# openScale_v04.net
KiCad netlist of a schematic drawn in EAGLE
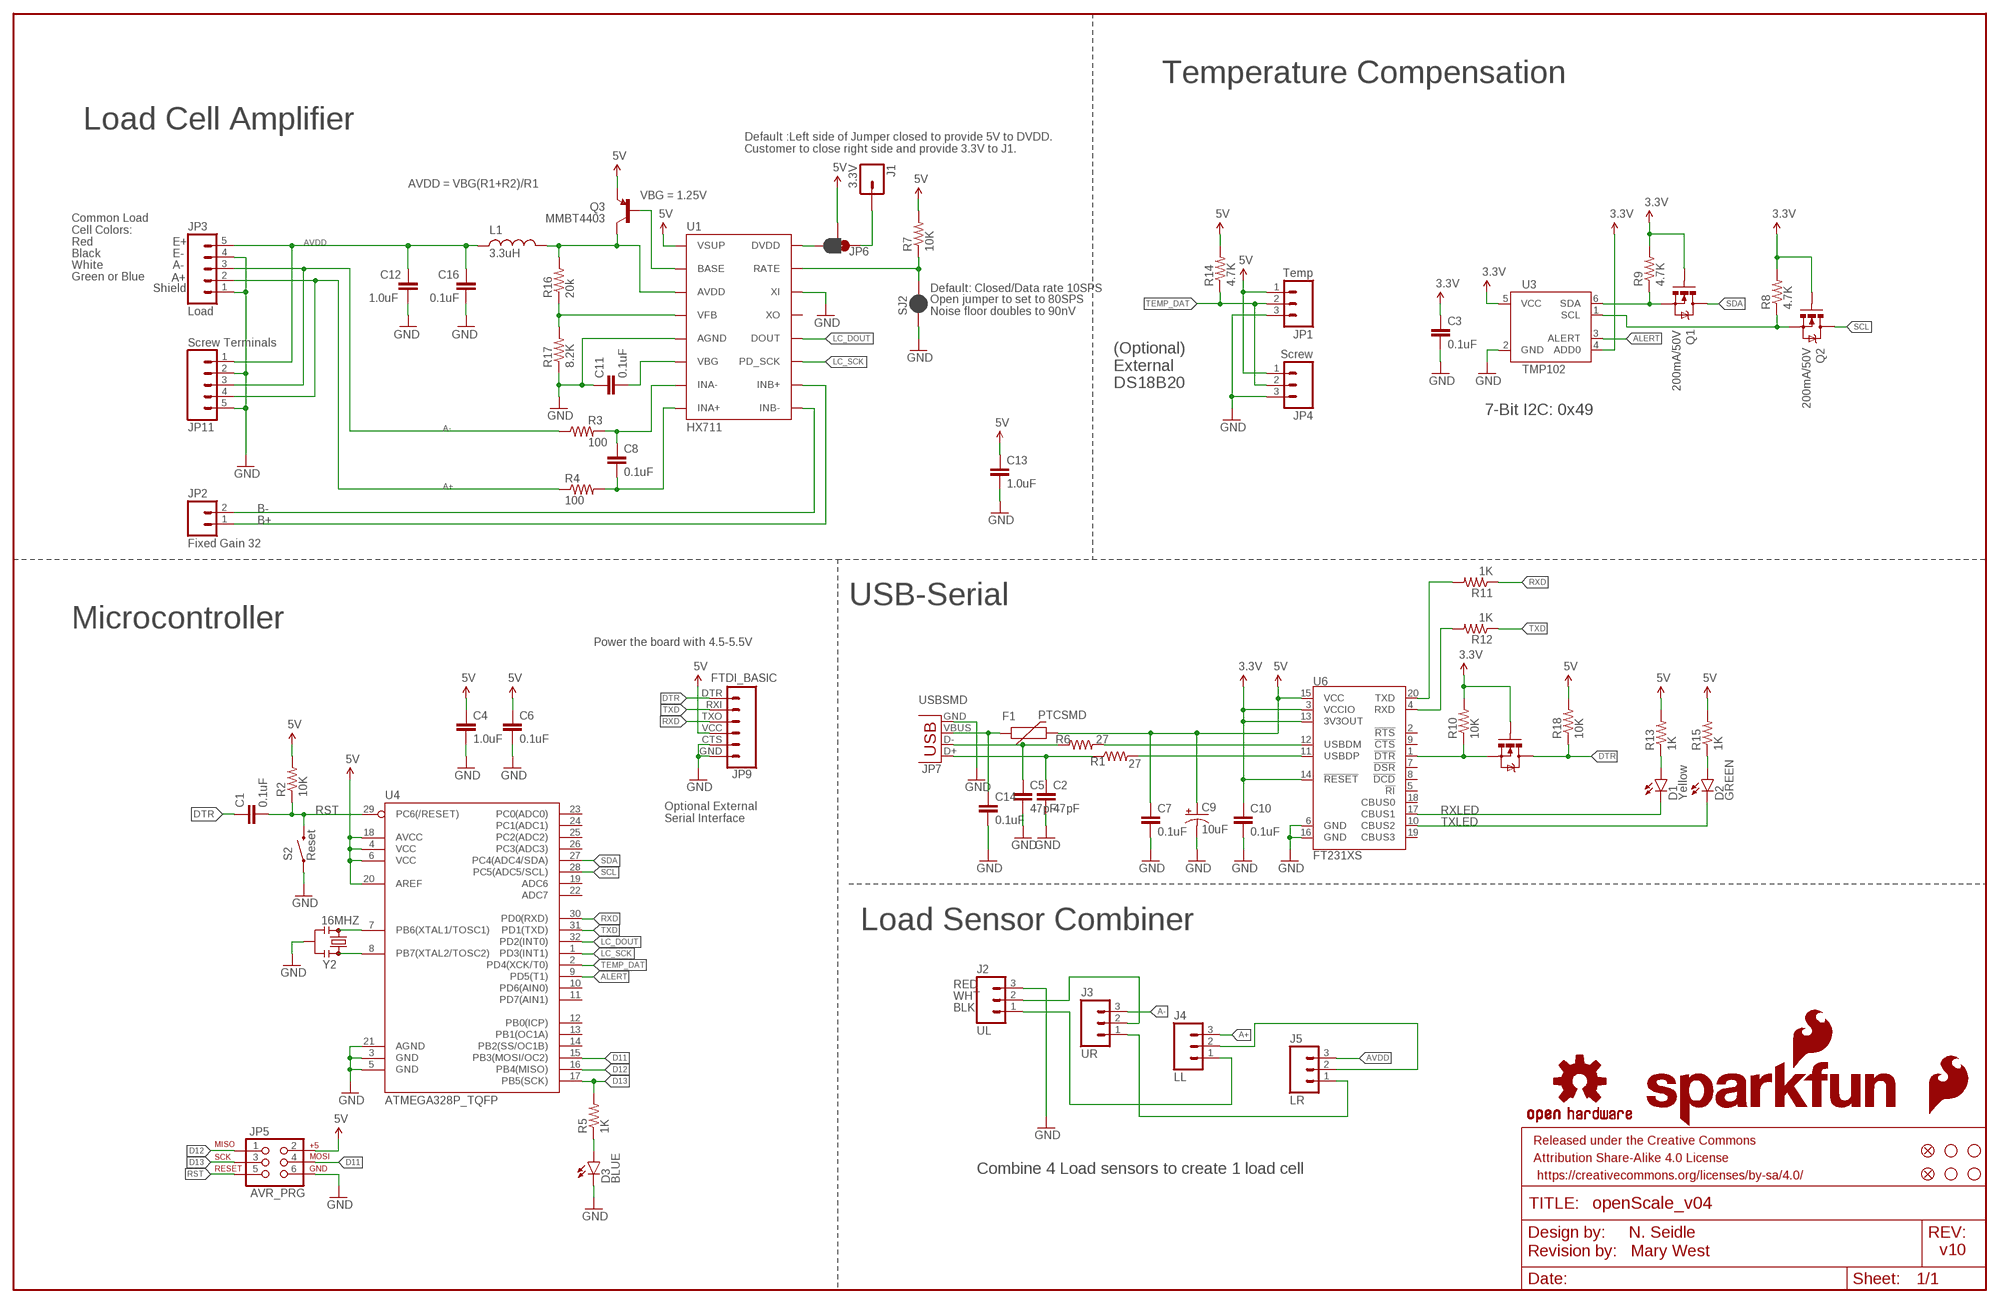
[diagram p0: schematic, sheet 1]

(export (version "E")
  (design (tool "Eeschema 10.0.6"))
  (components
    (comp (ref "C1")
      (value "0.1uF")
      (footprint "eagle-import:0603-CAP")
      (libsource (lib "eagle-import") (part "0.1UF-25V(+80/-20%)(0603)"))
    )
    (comp (ref "C2")
      (value "47pF")
      (footprint "eagle-import:0603-CAP")
      (libsource (lib "eagle-import") (part "47PF-50V-5%(0603)"))
    )
    (comp (ref "C3")
      (value "0.1uF")
      (footprint "eagle-import:0603-CAP")
      (libsource (lib "eagle-import") (part "0.1UF-25V(+80/-20%)(0603)"))
    )
    (comp (ref "C4")
      (value "1.0uF")
      (footprint "eagle-import:0603-CAP")
      (libsource (lib "eagle-import") (part "1.0UF-16V-10%(0603)"))
    )
    (comp (ref "C5")
      (value "47pF")
      (footprint "eagle-import:0603-CAP")
      (libsource (lib "eagle-import") (part "47PF-50V-5%(0603)"))
    )
    (comp (ref "C6")
      (value "0.1uF")
      (footprint "eagle-import:0603-CAP")
      (libsource (lib "eagle-import") (part "0.1UF-25V(+80/-20%)(0603)"))
    )
    (comp (ref "C7")
      (value "0.1uF")
      (footprint "eagle-import:0603-CAP")
      (libsource (lib "eagle-import") (part "0.1UF-25V(+80/-20%)(0603)"))
    )
    (comp (ref "C8")
      (value "0.1uF")
      (footprint "eagle-import:0603-CAP")
      (libsource (lib "eagle-import") (part "0.1UF-25V(+80/-20%)(0603)"))
    )
    (comp (ref "C9")
      (value "10uF")
      (footprint "eagle-import:EIA3216")
      (libsource (lib "eagle-import") (part "10UF-16V-10%(TANT)"))
    )
    (comp (ref "C10")
      (value "0.1uF")
      (footprint "eagle-import:0603-CAP")
      (libsource (lib "eagle-import") (part "0.1UF-25V(+80/-20%)(0603)"))
    )
    (comp (ref "C11")
      (value "0.1uF")
      (footprint "eagle-import:0603-CAP")
      (libsource (lib "eagle-import") (part "0.1UF-25V(+80/-20%)(0603)"))
    )
    (comp (ref "C12")
      (value "1.0uF")
      (footprint "eagle-import:0603-CAP")
      (libsource (lib "eagle-import") (part "1.0UF-16V-10%(0603)"))
    )
    (comp (ref "C13")
      (value "1.0uF")
      (footprint "eagle-import:0603-CAP")
      (libsource (lib "eagle-import") (part "1.0UF-16V-10%(0603)"))
    )
    (comp (ref "C14")
      (value "0.1uF")
      (footprint "eagle-import:0603-CAP")
      (libsource (lib "eagle-import") (part "0.1UF-25V(+80/-20%)(0603)"))
    )
    (comp (ref "C16")
      (value "0.1uF")
      (footprint "eagle-import:0603-CAP")
      (libsource (lib "eagle-import") (part "0.1UF-25V(+80/-20%)(0603)"))
    )
    (comp (ref "D1")
      (value "Yellow")
      (footprint "eagle-import:LED-1206")
      (libsource (lib "eagle-import") (part "LED-YELLOWLILYPAD"))
    )
    (comp (ref "D2")
      (value "GREEN")
      (footprint "eagle-import:LED-1206")
      (libsource (lib "eagle-import") (part "LED-GREEN1206"))
    )
    (comp (ref "D3")
      (value "BLUE")
      (footprint "eagle-import:LED-1206")
      (libsource (lib "eagle-import") (part "LED-BLUE1206"))
    )
    (comp (ref "F1")
      (value "PTCSMD")
      (footprint "eagle-import:PTC-1206")
      (libsource (lib "eagle-import") (part "PTCSMD"))
    )
    (comp (ref "FID1")
      (value "FIDUCIALUFIDUCIAL")
      (footprint "eagle-import:MICRO-FIDUCIAL")
      (libsource (lib "eagle-import") (part "FIDUCIALUFIDUCIAL"))
    )
    (comp (ref "FID2")
      (value "FIDUCIALUFIDUCIAL")
      (footprint "eagle-import:MICRO-FIDUCIAL")
      (libsource (lib "eagle-import") (part "FIDUCIALUFIDUCIAL"))
    )
    (comp (ref "FRAME1")
      (value "FRAME-LEDGER")
      (footprint "eagle-import:CREATIVE_COMMONS")
      (fields (field (name "DESIGNER") "N. Seidle") (field (name "VERSION") "v02"))
      (libsource (lib "eagle-import") (part "FRAME-LEDGER"))
    )
    (comp (ref "J1")
      (value "3.3V")
      (footprint "eagle-import:1X01")
      (libsource (lib "eagle-import") (part "M01PTH"))
    )
    (comp (ref "J2")
      (value "UL")
      (footprint "eagle-import:1X03")
      (libsource (lib "eagle-import") (part "M03PTH"))
    )
    (comp (ref "J3")
      (value "UR")
      (footprint "eagle-import:1X03")
      (libsource (lib "eagle-import") (part "M03PTH"))
    )
    (comp (ref "J4")
      (value "LL")
      (footprint "eagle-import:1X03")
      (libsource (lib "eagle-import") (part "M03PTH"))
    )
    (comp (ref "J5")
      (value "LR")
      (footprint "eagle-import:1X03")
      (libsource (lib "eagle-import") (part "M03PTH"))
    )
    (comp (ref "JP1")
      (value "Temp")
      (footprint "eagle-import:1X03_NO_SILK")
      (libsource (lib "eagle-import") (part "M031X03_NO_SILK"))
    )
    (comp (ref "JP2")
      (value "Fixed Gain 32")
      (footprint "eagle-import:1X02")
      (libsource (lib "eagle-import") (part "M02PTH"))
    )
    (comp (ref "JP3")
      (value "Load")
      (footprint "eagle-import:1X05_NO_SILK")
      (libsource (lib "eagle-import") (part "M05NO_SILK"))
    )
    (comp (ref "JP4")
      (value "Screw")
      (footprint "eagle-import:SCREWTERMINAL-3.5MM-3_LOCK.007S")
      (libsource (lib "eagle-import") (part "M03SCREW_LOCK"))
    )
    (comp (ref "JP5")
      (value "AVR_PRG")
      (footprint "eagle-import:2X3")
      (libsource (lib "eagle-import") (part "AVR_SPI_PRG_6PTH"))
    )
    (comp (ref "JP6")
      (value "JUMPER-PAD-3-2OF3_NC_BY_PASTE")
      (footprint "eagle-import:PAD-JUMPER-3-2OF3_NC_BY_PASTE_YES_SILK_FULL_BOX")
      (libsource (lib "eagle-import") (part "JUMPER-PAD-3-2OF3_NC_BY_PASTE"))
    )
    (comp (ref "JP7")
      (value "USBSMD")
      (footprint "eagle-import:USB-MINIB")
      (libsource (lib "eagle-import") (part "USBSMD"))
    )
    (comp (ref "JP9")
      (value "FTDI_BASIC")
      (footprint "eagle-import:FTDI_BASIC")
      (libsource (lib "eagle-import") (part "FTDI_BASICPTH"))
    )
    (comp (ref "JP11")
      (value "Screw Terminals")
      (footprint "eagle-import:SCREWTERMINAL-3.5MM-5")
      (libsource (lib "eagle-import") (part "M05SCREW"))
    )
    (comp (ref "L1")
      (value "3.3uH")
      (footprint "eagle-import:0805")
      (libsource (lib "eagle-import") (part "INDUCTOR0805-IND"))
    )
    (comp (ref "LOGO2")
      (value "OSHW-LOGOS")
      (footprint "eagle-import:OSHW-LOGO-S")
      (libsource (lib "eagle-import") (part "OSHW-LOGOS"))
    )
    (comp (ref "LOGO3")
      (value "SFE_LOGO_FLAME.1_INCH")
      (footprint "eagle-import:SFE_LOGO_FLAME_.1")
      (libsource (lib "eagle-import") (part "SFE_LOGO_FLAME.1_INCH"))
    )
    (comp (ref "LOGO4")
      (value "SFE_LOGO_NAME_FLAME.1_INCH")
      (footprint "eagle-import:SFE_LOGO_NAME_FLAME_.1")
      (libsource (lib "eagle-import") (part "SFE_LOGO_NAME_FLAME.1_INCH"))
    )
    (comp (ref "Q1")
      (value "200mA/50V")
      (footprint "eagle-import:SOT23-3")
      (libsource (lib "eagle-import") (part "MOSFET-NCHANNELBSS138"))
    )
    (comp (ref "Q2")
      (value "200mA/50V")
      (footprint "eagle-import:SOT23-3")
      (libsource (lib "eagle-import") (part "MOSFET-NCHANNELBSS138"))
    )
    (comp (ref "Q3")
      (value "MMBT4403")
      (footprint "eagle-import:SOT23-3")
      (libsource (lib "eagle-import") (part "TRANSISTOR_PNPMMBT4403"))
    )
    (comp (ref "Q4")
      (value "MOSFET-NCHANNEL2N7002PW")
      (footprint "eagle-import:SOT323")
      (libsource (lib "eagle-import") (part "MOSFET-NCHANNEL2N7002PW"))
    )
    (comp (ref "R1")
      (value "27")
      (footprint "eagle-import:0603")
      (libsource (lib "eagle-import") (part "27OHM1/10W1%(0603)"))
    )
    (comp (ref "R2")
      (value "10K")
      (footprint "eagle-import:0603-RES")
      (libsource (lib "eagle-import") (part "10KOHM-1/10W-1%(0603)0603"))
    )
    (comp (ref "R3")
      (value "100")
      (footprint "eagle-import:0603-RES")
      (libsource (lib "eagle-import") (part "100OHM-1/10W-1%(0603)"))
    )
    (comp (ref "R4")
      (value "100")
      (footprint "eagle-import:0603-RES")
      (libsource (lib "eagle-import") (part "100OHM-1/10W-1%(0603)"))
    )
    (comp (ref "R5")
      (value "1K")
      (footprint "eagle-import:0603-RES")
      (libsource (lib "eagle-import") (part "1KOHM-1/10W-1%(0603)"))
    )
    (comp (ref "R6")
      (value "27")
      (footprint "eagle-import:0603")
      (libsource (lib "eagle-import") (part "27OHM1/10W1%(0603)"))
    )
    (comp (ref "R7")
      (value "10K")
      (footprint "eagle-import:0603-RES")
      (libsource (lib "eagle-import") (part "10KOHM-1/10W-1%(0603)0603"))
    )
    (comp (ref "R8")
      (value "4.7K")
      (footprint "eagle-import:0603-RES")
      (libsource (lib "eagle-import") (part "4.7KOHM-1/10W-1%(0603)"))
    )
    (comp (ref "R9")
      (value "4.7K")
      (footprint "eagle-import:0603-RES")
      (libsource (lib "eagle-import") (part "4.7KOHM-1/10W-1%(0603)"))
    )
    (comp (ref "R10")
      (value "10K")
      (footprint "eagle-import:0603-RES")
      (libsource (lib "eagle-import") (part "10KOHM-1/10W-1%(0603)0603"))
    )
    (comp (ref "R11")
      (value "1K")
      (footprint "eagle-import:0603-RES")
      (libsource (lib "eagle-import") (part "1KOHM-1/10W-1%(0603)"))
    )
    (comp (ref "R12")
      (value "1K")
      (footprint "eagle-import:0603-RES")
      (libsource (lib "eagle-import") (part "1KOHM-1/10W-1%(0603)"))
    )
    (comp (ref "R13")
      (value "1K")
      (footprint "eagle-import:0603-RES")
      (libsource (lib "eagle-import") (part "1KOHM-1/10W-1%(0603)"))
    )
    (comp (ref "R14")
      (value "4.7K")
      (footprint "eagle-import:0603-RES")
      (libsource (lib "eagle-import") (part "4.7KOHM-1/10W-1%(0603)"))
    )
    (comp (ref "R15")
      (value "1K")
      (footprint "eagle-import:0603-RES")
      (libsource (lib "eagle-import") (part "1KOHM-1/10W-1%(0603)"))
    )
    (comp (ref "R16")
      (value "20k")
      (footprint "eagle-import:0603-RES")
      (libsource (lib "eagle-import") (part "20KOHM1/10W1%(0603)"))
    )
    (comp (ref "R17")
      (value "8.2K")
      (footprint "eagle-import:0603-RES")
      (libsource (lib "eagle-import") (part "8.2KOHM-1/10W-5%(0603)"))
    )
    (comp (ref "R18")
      (value "10K")
      (footprint "eagle-import:0603-RES")
      (libsource (lib "eagle-import") (part "10KOHM-1/10W-1%(0603)0603"))
    )
    (comp (ref "S2")
      (value "Reset")
      (footprint "eagle-import:TACTILE-SWITCH-SMD")
      (libsource (lib "eagle-import") (part "SWITCH-MOMENTARY-2SMD"))
    )
    (comp (ref "SJ2")
      (value "JUMPER-PAD-2-NC_BY_PASTE")
      (footprint "eagle-import:PAD-JUMPER-2-NC_BY_PASTE_YES_SILK")
      (libsource (lib "eagle-import") (part "JUMPER-PAD-2-NC_BY_PASTE"))
    )
    (comp (ref "STANDOFF1")
      (value "STAND-OFF")
      (footprint "eagle-import:STAND-OFF")
      (libsource (lib "eagle-import") (part "STAND-OFF"))
    )
    (comp (ref "STANDOFF2")
      (value "STAND-OFF")
      (footprint "eagle-import:STAND-OFF")
      (libsource (lib "eagle-import") (part "STAND-OFF"))
    )
    (comp (ref "STANDOFF3")
      (value "STAND-OFF")
      (footprint "eagle-import:STAND-OFF")
      (libsource (lib "eagle-import") (part "STAND-OFF"))
    )
    (comp (ref "STANDOFF4")
      (value "STAND-OFF")
      (footprint "eagle-import:STAND-OFF")
      (libsource (lib "eagle-import") (part "STAND-OFF"))
    )
    (comp (ref "U1")
      (value "HX711")
      (footprint "eagle-import:SO16")
      (libsource (lib "eagle-import") (part "HX711HX711"))
    )
    (comp (ref "U3")
      (value "TMP102")
      (footprint "eagle-import:SOT563")
      (libsource (lib "eagle-import") (part "TMP102"))
    )
    (comp (ref "U4")
      (value "ATMEGA328P_TQFP")
      (footprint "eagle-import:TQFP32-08")
      (libsource (lib "eagle-import") (part "ATMEGA328P_TQFP"))
    )
    (comp (ref "U6")
      (value "FT231XS")
      (footprint "eagle-import:SSOP20_L")
      (libsource (lib "eagle-import") (part "FT231XS"))
    )
    (comp (ref "Y2")
      (value "16MHZ")
      (footprint "eagle-import:RESONATOR-SMD")
      (libsource (lib "eagle-import") (part "RESONATOR16MHZ"))
    )
  )
  (nets
    (net (code "1") (name "/B+") (class "Default")
      (node (ref "JP2") (pin "1") (pinfunction "1_1") (pintype "passive"))
      (node (ref "U1") (pin "10") (pinfunction "INB+_10") (pintype "bidirectional"))
    )
    (net (code "2") (name "/B-") (class "Default")
      (node (ref "JP2") (pin "2") (pinfunction "2_2") (pintype "passive"))
      (node (ref "U1") (pin "9") (pinfunction "INB-_9") (pintype "bidirectional"))
    )
    (net (code "3") (name "/RXLED") (class "Default")
      (node (ref "D1") (pin "C") (pinfunction "C_C") (pintype "passive"))
      (node (ref "U6") (pin "17") (pinfunction "CBUS1_17") (pintype "bidirectional"))
    )
    (net (code "4") (name "/TXLED") (class "Default")
      (node (ref "D2") (pin "C") (pinfunction "C_C") (pintype "passive"))
      (node (ref "U6") (pin "10") (pinfunction "CBUS2_10") (pintype "bidirectional"))
    )
    (net (code "5") (name "3.3V") (class "Default")
      (node (ref "C10") (pin "1") (pinfunction "1_1") (pintype "passive"))
      (node (ref "C3") (pin "1") (pinfunction "1_1") (pintype "passive"))
      (node (ref "Q1") (pin "1") (pinfunction "G_1") (pintype "passive"))
      (node (ref "Q2") (pin "1") (pinfunction "G_1") (pintype "passive"))
      (node (ref "Q4") (pin "1") (pinfunction "G_1") (pintype "passive"))
      (node (ref "R10") (pin "2") (pinfunction "2_2") (pintype "passive"))
      (node (ref "R8") (pin "2") (pinfunction "2_2") (pintype "passive"))
      (node (ref "R9") (pin "2") (pinfunction "2_2") (pintype "passive"))
      (node (ref "U3") (pin "4") (pinfunction "ADD0_4") (pintype "bidirectional"))
      (node (ref "U3") (pin "5") (pinfunction "VCC_5") (pintype "bidirectional"))
      (node (ref "U6") (pin "13") (pinfunction "3V3OUT_13") (pintype "bidirectional"))
      (node (ref "U6") (pin "14") (pinfunction "~{RESET}_14") (pintype "bidirectional"))
      (node (ref "U6") (pin "3") (pinfunction "VCCIO_3") (pintype "bidirectional"))
    )
    (net (code "6") (name "5V") (class "Default")
      (node (ref "C13") (pin "1") (pinfunction "1_1") (pintype "passive"))
      (node (ref "C4") (pin "1") (pinfunction "1_1") (pintype "passive"))
      (node (ref "C6") (pin "1") (pinfunction "1_1") (pintype "passive"))
      (node (ref "C7") (pin "1") (pinfunction "1_1") (pintype "passive"))
      (node (ref "C9") (pin "A") (pinfunction "+_A") (pintype "passive"))
      (node (ref "F1") (pin "2") (pinfunction "2_2") (pintype "bidirectional"))
      (node (ref "JP1") (pin "1") (pinfunction "1_1") (pintype "passive"))
      (node (ref "JP4") (pin "1") (pinfunction "1_1") (pintype "passive"))
      (node (ref "JP5") (pin "2") (pinfunction "2_2") (pintype "passive"))
      (node (ref "JP6") (pin "2") (pinfunction "2_2") (pintype "passive"))
      (node (ref "JP9") (pin "VCC") (pinfunction "4_VCC") (pintype "passive"))
      (node (ref "Q3") (pin "2") (pinfunction "E_2") (pintype "passive"))
      (node (ref "R13") (pin "2") (pinfunction "2_2") (pintype "passive"))
      (node (ref "R14") (pin "2") (pinfunction "2_2") (pintype "passive"))
      (node (ref "R15") (pin "2") (pinfunction "2_2") (pintype "passive"))
      (node (ref "R18") (pin "2") (pinfunction "2_2") (pintype "passive"))
      (node (ref "R2") (pin "2") (pinfunction "2_2") (pintype "passive"))
      (node (ref "R7") (pin "2") (pinfunction "2_2") (pintype "passive"))
      (node (ref "U1") (pin "1") (pinfunction "VSUP_1") (pintype "bidirectional"))
      (node (ref "U4") (pin "18") (pinfunction "AVCC_18") (pintype "bidirectional"))
      (node (ref "U4") (pin "20") (pinfunction "AREF_20") (pintype "bidirectional"))
      (node (ref "U4") (pin "4") (pinfunction "VCC_4") (pintype "bidirectional"))
      (node (ref "U4") (pin "6") (pinfunction "VCC_6") (pintype "bidirectional"))
      (node (ref "U6") (pin "15") (pinfunction "VCC_15") (pintype "bidirectional"))
    )
    (net (code "7") (name "A+") (class "Default")
      (node (ref "J4") (pin "3") (pinfunction "3_3") (pintype "passive"))
      (node (ref "JP11") (pin "4") (pinfunction "4_4") (pintype "passive"))
      (node (ref "JP3") (pin "2") (pinfunction "2_2") (pintype "passive"))
      (node (ref "R4") (pin "1") (pinfunction "1_1") (pintype "passive"))
    )
    (net (code "8") (name "A-") (class "Default")
      (node (ref "J3") (pin "3") (pinfunction "3_3") (pintype "passive"))
      (node (ref "JP11") (pin "3") (pinfunction "3_3") (pintype "passive"))
      (node (ref "JP3") (pin "3") (pinfunction "3_3") (pintype "passive"))
      (node (ref "R3") (pin "1") (pinfunction "1_1") (pintype "passive"))
    )
    (net (code "9") (name "ALERT") (class "Default")
      (node (ref "U3") (pin "3") (pinfunction "ALERT_3") (pintype "bidirectional"))
      (node (ref "U4") (pin "9") (pinfunction "PD5(T1)_9") (pintype "bidirectional"))
    )
    (net (code "10") (name "AVDD") (class "Default")
      (node (ref "C12") (pin "2") (pinfunction "2_2") (pintype "passive"))
      (node (ref "C16") (pin "1") (pinfunction "1_1") (pintype "passive"))
      (node (ref "J5") (pin "3") (pinfunction "3_3") (pintype "passive"))
      (node (ref "JP11") (pin "1") (pinfunction "1_1") (pintype "passive"))
      (node (ref "JP3") (pin "5") (pinfunction "5_5") (pintype "passive"))
      (node (ref "L1") (pin "1") (pinfunction "1_1") (pintype "passive"))
    )
    (net (code "11") (name "D11") (class "Default")
      (node (ref "JP5") (pin "4") (pinfunction "4_4") (pintype "passive"))
      (node (ref "U4") (pin "15") (pinfunction "PB3(MOSI/OC2)_15") (pintype "bidirectional"))
    )
    (net (code "12") (name "D12") (class "Default")
      (node (ref "JP5") (pin "1") (pinfunction "1_1") (pintype "passive"))
      (node (ref "U4") (pin "16") (pinfunction "PB4(MISO)_16") (pintype "bidirectional"))
    )
    (net (code "13") (name "D13") (class "Default")
      (node (ref "JP5") (pin "3") (pinfunction "3_3") (pintype "passive"))
      (node (ref "R5") (pin "2") (pinfunction "2_2") (pintype "passive"))
      (node (ref "U4") (pin "17") (pinfunction "PB5(SCK)_17") (pintype "bidirectional"))
    )
    (net (code "14") (name "DTR") (class "Default")
      (node (ref "C1") (pin "1") (pinfunction "1_1") (pintype "passive"))
      (node (ref "JP9") (pin "DTR") (pinfunction "1_DTR") (pintype "passive"))
      (node (ref "Q4") (pin "3") (pinfunction "D_3") (pintype "passive"))
      (node (ref "R18") (pin "1") (pinfunction "1_1") (pintype "passive"))
    )
    (net (code "15") (name "GND") (class "Default")
      (node (ref "C10") (pin "2") (pinfunction "2_2") (pintype "passive"))
      (node (ref "C11") (pin "1") (pinfunction "1_1") (pintype "passive"))
      (node (ref "C12") (pin "1") (pinfunction "1_1") (pintype "passive"))
      (node (ref "C13") (pin "2") (pinfunction "2_2") (pintype "passive"))
      (node (ref "C14") (pin "2") (pinfunction "2_2") (pintype "passive"))
      (node (ref "C16") (pin "2") (pinfunction "2_2") (pintype "passive"))
      (node (ref "C2") (pin "2") (pinfunction "2_2") (pintype "passive"))
      (node (ref "C3") (pin "2") (pinfunction "2_2") (pintype "passive"))
      (node (ref "C4") (pin "2") (pinfunction "2_2") (pintype "passive"))
      (node (ref "C5") (pin "2") (pinfunction "2_2") (pintype "passive"))
      (node (ref "C6") (pin "2") (pinfunction "2_2") (pintype "passive"))
      (node (ref "C7") (pin "2") (pinfunction "2_2") (pintype "passive"))
      (node (ref "C9") (pin "C") (pinfunction "-_C") (pintype "passive"))
      (node (ref "D3") (pin "C") (pinfunction "C_C") (pintype "passive"))
      (node (ref "J2") (pin "3") (pinfunction "3_3") (pintype "passive"))
      (node (ref "JP1") (pin "3") (pinfunction "3_3") (pintype "passive"))
      (node (ref "JP11") (pin "2") (pinfunction "2_2") (pintype "passive"))
      (node (ref "JP11") (pin "5") (pinfunction "5_5") (pintype "passive"))
      (node (ref "JP3") (pin "1") (pinfunction "1_1") (pintype "passive"))
      (node (ref "JP3") (pin "4") (pinfunction "4_4") (pintype "passive"))
      (node (ref "JP4") (pin "3") (pinfunction "3_3") (pintype "passive"))
      (node (ref "JP5") (pin "6") (pinfunction "6_6") (pintype "passive"))
      (node (ref "JP7") (pin "GND") (pinfunction "GND_GND") (pintype "bidirectional"))
      (node (ref "JP9") (pin "CTS") (pinfunction "5_CTS") (pintype "passive"))
      (node (ref "JP9") (pin "GND") (pinfunction "6_GND") (pintype "passive"))
      (node (ref "R17") (pin "1") (pinfunction "1_1") (pintype "passive"))
      (node (ref "S2") (pin "1") (pinfunction "1_1") (pintype "passive"))
      (node (ref "SJ2") (pin "1") (pinfunction "1_1") (pintype "passive"))
      (node (ref "U1") (pin "14") (pinfunction "XI_14") (pintype "bidirectional"))
      (node (ref "U1") (pin "5") (pinfunction "AGND_5") (pintype "bidirectional"))
      (node (ref "U3") (pin "2") (pinfunction "GND_2") (pintype "bidirectional"))
      (node (ref "U4") (pin "21") (pinfunction "AGND_21") (pintype "bidirectional"))
      (node (ref "U4") (pin "3") (pinfunction "GND_3") (pintype "bidirectional"))
      (node (ref "U4") (pin "5") (pinfunction "GND_5") (pintype "bidirectional"))
      (node (ref "U6") (pin "16") (pinfunction "GND_16") (pintype "bidirectional"))
      (node (ref "U6") (pin "6") (pinfunction "GND_6") (pintype "bidirectional"))
      (node (ref "Y2") (pin "2") (pinfunction "2_2") (pintype "passive"))
    )
    (net (code "16") (name "LC_DOUT") (class "Default")
      (node (ref "U1") (pin "12") (pinfunction "DOUT_12") (pintype "bidirectional"))
      (node (ref "U4") (pin "32") (pinfunction "PD2(INT0)_32") (pintype "bidirectional"))
    )
    (net (code "17") (name "LC_SCK") (class "Default")
      (node (ref "U1") (pin "11") (pinfunction "PD_SCK_11") (pintype "bidirectional"))
      (node (ref "U4") (pin "1") (pinfunction "PD3(INT1)_1") (pintype "bidirectional"))
    )
    (net (code "18") (name "Net-(C2-Pad1)") (class "Default")
      (node (ref "C2") (pin "1") (pinfunction "1_1") (pintype "passive"))
      (node (ref "JP7") (pin "D+") (pinfunction "D+_D+") (pintype "bidirectional"))
      (node (ref "R1") (pin "1") (pinfunction "1_1") (pintype "passive"))
    )
    (net (code "19") (name "Net-(C5-Pad1)") (class "Default")
      (node (ref "C5") (pin "1") (pinfunction "1_1") (pintype "passive"))
      (node (ref "JP7") (pin "D-") (pinfunction "D-_D-") (pintype "bidirectional"))
      (node (ref "R6") (pin "1") (pinfunction "1_1") (pintype "passive"))
    )
    (net (code "20") (name "Net-(C14-Pad1)") (class "Default")
      (node (ref "C14") (pin "1") (pinfunction "1_1") (pintype "passive"))
      (node (ref "F1") (pin "1") (pinfunction "1_1") (pintype "bidirectional"))
      (node (ref "JP7") (pin "VBUS") (pinfunction "VBUS_VBUS") (pintype "bidirectional"))
    )
    (net (code "21") (name "Net-(D1-PadA)") (class "Default")
      (node (ref "D1") (pin "A") (pinfunction "A_A") (pintype "passive"))
      (node (ref "R13") (pin "1") (pinfunction "1_1") (pintype "passive"))
    )
    (net (code "22") (name "Net-(D2-PadA)") (class "Default")
      (node (ref "D2") (pin "A") (pinfunction "A_A") (pintype "passive"))
      (node (ref "R15") (pin "1") (pinfunction "1_1") (pintype "passive"))
    )
    (net (code "23") (name "Net-(D3-PadA)") (class "Default")
      (node (ref "D3") (pin "A") (pinfunction "A_A") (pintype "passive"))
      (node (ref "R5") (pin "1") (pinfunction "1_1") (pintype "passive"))
    )
    (net (code "24") (name "Net-(J1-Pad1)") (class "Default")
      (node (ref "J1") (pin "1") (pinfunction "1_1") (pintype "passive"))
      (node (ref "JP6") (pin "1") (pinfunction "1_1") (pintype "passive"))
    )
    (net (code "25") (name "Net-(J2-Pad1)") (class "Default")
      (node (ref "J2") (pin "1") (pinfunction "1_1") (pintype "passive"))
      (node (ref "J4") (pin "1") (pinfunction "1_1") (pintype "passive"))
    )
    (net (code "26") (name "Net-(J2-Pad2)") (class "Default")
      (node (ref "J2") (pin "2") (pinfunction "2_2") (pintype "passive"))
      (node (ref "J3") (pin "2") (pinfunction "2_2") (pintype "passive"))
    )
    (net (code "27") (name "Net-(J3-Pad1)") (class "Default")
      (node (ref "J3") (pin "1") (pinfunction "1_1") (pintype "passive"))
      (node (ref "J5") (pin "1") (pinfunction "1_1") (pintype "passive"))
    )
    (net (code "28") (name "Net-(J4-Pad2)") (class "Default")
      (node (ref "J4") (pin "2") (pinfunction "2_2") (pintype "passive"))
      (node (ref "J5") (pin "2") (pinfunction "2_2") (pintype "passive"))
    )
    (net (code "29") (name "Net-(Q1-S)") (class "Default")
      (node (ref "Q1") (pin "2") (pinfunction "S_2") (pintype "passive"))
      (node (ref "R9") (pin "1") (pinfunction "1_1") (pintype "passive"))
      (node (ref "U3") (pin "6") (pinfunction "SDA_6") (pintype "bidirectional"))
    )
    (net (code "30") (name "Net-(Q2-S)") (class "Default")
      (node (ref "Q2") (pin "2") (pinfunction "S_2") (pintype "passive"))
      (node (ref "R8") (pin "1") (pinfunction "1_1") (pintype "passive"))
      (node (ref "U3") (pin "1") (pinfunction "SCL_1") (pintype "bidirectional"))
    )
    (net (code "31") (name "Net-(Q3-B)") (class "Default")
      (node (ref "Q3") (pin "1") (pinfunction "B_1") (pintype "passive"))
      (node (ref "U1") (pin "2") (pinfunction "BASE_2") (pintype "bidirectional"))
    )
    (net (code "32") (name "Net-(Q3-C)") (class "Default")
      (node (ref "L1") (pin "2") (pinfunction "2_2") (pintype "passive"))
      (node (ref "Q3") (pin "3") (pinfunction "C_3") (pintype "passive"))
      (node (ref "R16") (pin "2") (pinfunction "2_2") (pintype "passive"))
      (node (ref "U1") (pin "3") (pinfunction "AVDD_3") (pintype "bidirectional"))
    )
    (net (code "33") (name "Net-(Q4-S)") (class "Default")
      (node (ref "Q4") (pin "2") (pinfunction "S_2") (pintype "passive"))
      (node (ref "R10") (pin "1") (pinfunction "1_1") (pintype "passive"))
      (node (ref "U6") (pin "1") (pinfunction "~{DTR}_1") (pintype "bidirectional"))
    )
    (net (code "34") (name "Net-(U1-DVDD)") (class "Default")
      (node (ref "JP6") (pin "3") (pinfunction "3_3") (pintype "passive"))
      (node (ref "U1") (pin "16") (pinfunction "DVDD_16") (pintype "bidirectional"))
    )
    (net (code "35") (name "Net-(U1-INA+)") (class "Default")
      (node (ref "C8") (pin "2") (pinfunction "2_2") (pintype "passive"))
      (node (ref "R4") (pin "2") (pinfunction "2_2") (pintype "passive"))
      (node (ref "U1") (pin "8") (pinfunction "INA+_8") (pintype "bidirectional"))
    )
    (net (code "36") (name "Net-(U1-INA-)") (class "Default")
      (node (ref "C8") (pin "1") (pinfunction "1_1") (pintype "passive"))
      (node (ref "R3") (pin "2") (pinfunction "2_2") (pintype "passive"))
      (node (ref "U1") (pin "7") (pinfunction "INA-_7") (pintype "bidirectional"))
    )
    (net (code "37") (name "Net-(U1-RATE)") (class "Default")
      (node (ref "R7") (pin "1") (pinfunction "1_1") (pintype "passive"))
      (node (ref "SJ2") (pin "2") (pinfunction "2_2") (pintype "passive"))
      (node (ref "U1") (pin "15") (pinfunction "RATE_15") (pintype "bidirectional"))
    )
    (net (code "38") (name "Net-(U1-VBG)") (class "Default")
      (node (ref "C11") (pin "2") (pinfunction "2_2") (pintype "passive"))
      (node (ref "U1") (pin "6") (pinfunction "VBG_6") (pintype "bidirectional"))
    )
    (net (code "39") (name "Net-(U1-VFB)") (class "Default")
      (node (ref "R16") (pin "1") (pinfunction "1_1") (pintype "passive"))
      (node (ref "R17") (pin "2") (pinfunction "2_2") (pintype "passive"))
      (node (ref "U1") (pin "4") (pinfunction "VFB_4") (pintype "bidirectional"))
    )
    (net (code "40") (name "Net-(U4-PB6(XTAL1{slash}TOSC1))") (class "Default")
      (node (ref "U4") (pin "7") (pinfunction "PB6(XTAL1/TOSC1)_7") (pintype "bidirectional"))
      (node (ref "Y2") (pin "1") (pinfunction "1_1") (pintype "passive"))
    )
    (net (code "41") (name "Net-(U4-PB7(XTAL2{slash}TOSC2))") (class "Default")
      (node (ref "U4") (pin "8") (pinfunction "PB7(XTAL2/TOSC2)_8") (pintype "bidirectional"))
      (node (ref "Y2") (pin "3") (pinfunction "3_3") (pintype "passive"))
    )
    (net (code "42") (name "Net-(U6-RXD)") (class "Default")
      (node (ref "R12") (pin "2") (pinfunction "2_2") (pintype "passive"))
      (node (ref "U6") (pin "4") (pinfunction "RXD_4") (pintype "bidirectional"))
    )
    (net (code "43") (name "Net-(U6-TXD)") (class "Default")
      (node (ref "R11") (pin "2") (pinfunction "2_2") (pintype "passive"))
      (node (ref "U6") (pin "20") (pinfunction "TXD_20") (pintype "bidirectional"))
    )
    (net (code "44") (name "Net-(U6-USBDM)") (class "Default")
      (node (ref "R6") (pin "2") (pinfunction "2_2") (pintype "passive"))
      (node (ref "U6") (pin "12") (pinfunction "USBDM_12") (pintype "bidirectional"))
    )
    (net (code "45") (name "Net-(U6-USBDP)") (class "Default")
      (node (ref "R1") (pin "2") (pinfunction "2_2") (pintype "passive"))
      (node (ref "U6") (pin "11") (pinfunction "USBDP_11") (pintype "bidirectional"))
    )
    (net (code "46") (name "RST") (class "Default")
      (node (ref "C1") (pin "2") (pinfunction "2_2") (pintype "passive"))
      (node (ref "JP5") (pin "5") (pinfunction "5_5") (pintype "passive"))
      (node (ref "R2") (pin "1") (pinfunction "1_1") (pintype "passive"))
      (node (ref "S2") (pin "3") (pinfunction "2_3") (pintype "passive"))
      (node (ref "U4") (pin "29") (pinfunction "PC6(/RESET)_29") (pintype "bidirectional"))
    )
    (net (code "47") (name "RXD") (class "Default")
      (node (ref "JP9") (pin "TXO") (pinfunction "3_TXO") (pintype "passive"))
      (node (ref "R11") (pin "1") (pinfunction "1_1") (pintype "passive"))
      (node (ref "U4") (pin "30") (pinfunction "PD0(RXD)_30") (pintype "bidirectional"))
    )
    (net (code "48") (name "SCL") (class "Default")
      (node (ref "Q2") (pin "3") (pinfunction "D_3") (pintype "passive"))
      (node (ref "U4") (pin "28") (pinfunction "PC5(ADC5/SCL)_28") (pintype "bidirectional"))
    )
    (net (code "49") (name "SDA") (class "Default")
      (node (ref "Q1") (pin "3") (pinfunction "D_3") (pintype "passive"))
      (node (ref "U4") (pin "27") (pinfunction "PC4(ADC4/SDA)_27") (pintype "bidirectional"))
    )
    (net (code "50") (name "TEMP_DAT") (class "Default")
      (node (ref "JP1") (pin "2") (pinfunction "2_2") (pintype "passive"))
      (node (ref "JP4") (pin "2") (pinfunction "2_2") (pintype "passive"))
      (node (ref "R14") (pin "1") (pinfunction "1_1") (pintype "passive"))
      (node (ref "U4") (pin "2") (pinfunction "PD4(XCK/T0)_2") (pintype "bidirectional"))
    )
    (net (code "51") (name "TXD") (class "Default")
      (node (ref "JP9") (pin "RXI") (pinfunction "2_RXI") (pintype "passive"))
      (node (ref "R12") (pin "1") (pinfunction "1_1") (pintype "passive"))
      (node (ref "U4") (pin "31") (pinfunction "PD1(TXD)_31") (pintype "bidirectional"))
    )
    (net (code "52") (name "unconnected-(U1-XO-Pad13)") (class "Default")
      (node (ref "U1") (pin "13") (pinfunction "XO_13") (pintype "bidirectional"))
    )
    (net (code "53") (name "unconnected-(U4-ADC6-Pad19)") (class "Default")
      (node (ref "U4") (pin "19") (pinfunction "ADC6_19") (pintype "bidirectional"))
    )
    (net (code "54") (name "unconnected-(U4-ADC7-Pad22)") (class "Default")
      (node (ref "U4") (pin "22") (pinfunction "ADC7_22") (pintype "bidirectional"))
    )
    (net (code "55") (name "unconnected-(U4-PB0(ICP)-Pad12)") (class "Default")
      (node (ref "U4") (pin "12") (pinfunction "PB0(ICP)_12") (pintype "bidirectional"))
    )
    (net (code "56") (name "unconnected-(U4-PB1(OC1A)-Pad13)") (class "Default")
      (node (ref "U4") (pin "13") (pinfunction "PB1(OC1A)_13") (pintype "bidirectional"))
    )
    (net (code "57") (name "unconnected-(U4-PB2(SS{slash}OC1B)-Pad14)") (class "Default")
      (node (ref "U4") (pin "14") (pinfunction "PB2(SS/OC1B)_14") (pintype "bidirectional"))
    )
    (net (code "58") (name "unconnected-(U4-PC0(ADC0)-Pad23)") (class "Default")
      (node (ref "U4") (pin "23") (pinfunction "PC0(ADC0)_23") (pintype "bidirectional"))
    )
    (net (code "59") (name "unconnected-(U4-PC1(ADC1)-Pad24)") (class "Default")
      (node (ref "U4") (pin "24") (pinfunction "PC1(ADC1)_24") (pintype "bidirectional"))
    )
    (net (code "60") (name "unconnected-(U4-PC2(ADC2)-Pad25)") (class "Default")
      (node (ref "U4") (pin "25") (pinfunction "PC2(ADC2)_25") (pintype "bidirectional"))
    )
    (net (code "61") (name "unconnected-(U4-PC3(ADC3)-Pad26)") (class "Default")
      (node (ref "U4") (pin "26") (pinfunction "PC3(ADC3)_26") (pintype "bidirectional"))
    )
    (net (code "62") (name "unconnected-(U4-PD6(AIN0)-Pad10)") (class "Default")
      (node (ref "U4") (pin "10") (pinfunction "PD6(AIN0)_10") (pintype "bidirectional"))
    )
    (net (code "63") (name "unconnected-(U4-PD7(AIN1)-Pad11)") (class "Default")
      (node (ref "U4") (pin "11") (pinfunction "PD7(AIN1)_11") (pintype "bidirectional"))
    )
    (net (code "64") (name "unconnected-(U6-CBUS0-Pad18)") (class "Default")
      (node (ref "U6") (pin "18") (pinfunction "CBUS0_18") (pintype "bidirectional"))
    )
    (net (code "65") (name "unconnected-(U6-CBUS3-Pad19)") (class "Default")
      (node (ref "U6") (pin "19") (pinfunction "CBUS3_19") (pintype "bidirectional"))
    )
    (net (code "66") (name "unconnected-(U6-~{CTS}-Pad9)") (class "Default")
      (node (ref "U6") (pin "9") (pinfunction "~{CTS}_9") (pintype "bidirectional"))
    )
    (net (code "67") (name "unconnected-(U6-~{DCD}-Pad8)") (class "Default")
      (node (ref "U6") (pin "8") (pinfunction "~{DCD}_8") (pintype "bidirectional"))
    )
    (net (code "68") (name "unconnected-(U6-~{DSR}-Pad7)") (class "Default")
      (node (ref "U6") (pin "7") (pinfunction "~{DSR}_7") (pintype "bidirectional"))
    )
    (net (code "69") (name "unconnected-(U6-~{RI}-Pad5)") (class "Default")
      (node (ref "U6") (pin "5") (pinfunction "~{RI}_5") (pintype "bidirectional"))
    )
    (net (code "70") (name "unconnected-(U6-~{RTS}-Pad2)") (class "Default")
      (node (ref "U6") (pin "2") (pinfunction "~{RTS}_2") (pintype "bidirectional"))
    )
  )
)
